# GarageRemote.net
KiCad netlist of a schematic drawn in EAGLE
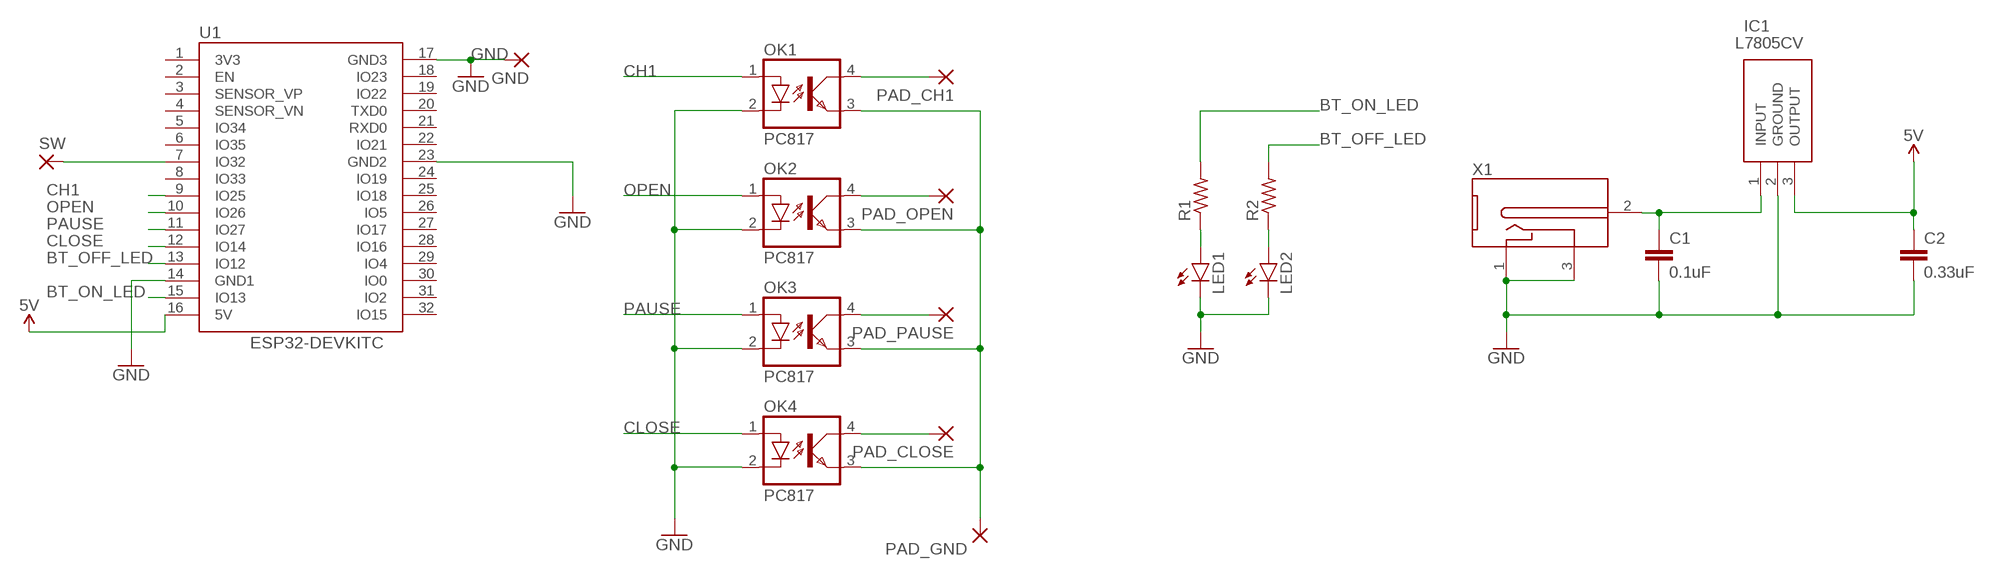
[diagram p0: schematic, sheet 1]

(export (version "E")
  (design (tool "Eeschema 10.0.6"))
  (components
    (comp (ref "C1")
      (value "0.1uF")
      (footprint "eagle-import:C2.5-2")
      (libsource (lib "eagle-import") (part "C2.5/2"))
    )
    (comp (ref "C2")
      (value "0.33uF")
      (footprint "eagle-import:C2.5-2")
      (libsource (lib "eagle-import") (part "C2.5/2"))
    )
    (comp (ref "GND")
      (value "2,54/1,0")
      (footprint "eagle-import:2,54_1,0")
      (libsource (lib "eagle-import") (part "2,54/1,0"))
    )
    (comp (ref "IC1")
      (value "L7805CV")
      (footprint "eagle-import:TO255P460X1020X2008-3P")
      (fields (field (name "MOUSER_PART_NUMBER") "511-L7805CV"))
      (libsource (lib "eagle-import") (part "L7805CV"))
    )
    (comp (ref "LED1")
      (value "LED5MM")
      (footprint "eagle-import:LED5MM")
      (libsource (lib "eagle-import") (part "LED5MM"))
    )
    (comp (ref "LED2")
      (value "LED5MM")
      (footprint "eagle-import:LED5MM")
      (libsource (lib "eagle-import") (part "LED5MM"))
    )
    (comp (ref "OK1")
      (value "PC817")
      (footprint "eagle-import:DIL04")
      (fields (field (name "MPN") "PC817X4J000F"))
      (libsource (lib "eagle-import") (part "PC817"))
    )
    (comp (ref "OK2")
      (value "PC817")
      (footprint "eagle-import:DIL04")
      (fields (field (name "MPN") "PC817X4J000F"))
      (libsource (lib "eagle-import") (part "PC817"))
    )
    (comp (ref "OK3")
      (value "PC817")
      (footprint "eagle-import:DIL04")
      (fields (field (name "MPN") "PC817X4J000F"))
      (libsource (lib "eagle-import") (part "PC817"))
    )
    (comp (ref "OK4")
      (value "PC817")
      (footprint "eagle-import:DIL04")
      (fields (field (name "MPN") "PC817X4J000F"))
      (libsource (lib "eagle-import") (part "PC817"))
    )
    (comp (ref "PAD_CH1")
      (value "2,54/1,0")
      (footprint "eagle-import:2,54_1,0")
      (libsource (lib "eagle-import") (part "2,54/1,0"))
    )
    (comp (ref "PAD_CLOSE")
      (value "2,54/1,0")
      (footprint "eagle-import:2,54_1,0")
      (libsource (lib "eagle-import") (part "2,54/1,0"))
    )
    (comp (ref "PAD_GND")
      (value "2,54/1,0")
      (footprint "eagle-import:2,54_1,0")
      (libsource (lib "eagle-import") (part "2,54/1,0"))
    )
    (comp (ref "PAD_OPEN")
      (value "2,54/1,0")
      (footprint "eagle-import:2,54_1,0")
      (libsource (lib "eagle-import") (part "2,54/1,0"))
    )
    (comp (ref "PAD_PAUSE")
      (value "2,54/1,0")
      (footprint "eagle-import:2,54_1,0")
      (libsource (lib "eagle-import") (part "2,54/1,0"))
    )
    (comp (ref "R1")
      (value "R-US_0204/5")
      (footprint "eagle-import:0204_5")
      (libsource (lib "eagle-import") (part "R-US_0204/5"))
    )
    (comp (ref "R2")
      (value "R-US_0204/5")
      (footprint "eagle-import:0204_5")
      (libsource (lib "eagle-import") (part "R-US_0204/5"))
    )
    (comp (ref "SW")
      (value "2,54/1,0")
      (footprint "eagle-import:2,54_1,0")
      (libsource (lib "eagle-import") (part "2,54/1,0"))
    )
    (comp (ref "U1")
      (value "ESP32-DEVKITC")
      (footprint "eagle-import:MODULE_ESP32-DEVKITC")
      (fields (field (name "MF") "Espressif Systems"))
      (libsource (lib "eagle-import") (part "ESP32-DEVKITC"))
    )
    (comp (ref "X1")
      (value "DC-2.1MM-5MM")
      (footprint "eagle-import:DC-21MM")
      (libsource (lib "eagle-import") (part "DC-5MM-2.1MM"))
    )
  )
  (nets
    (net (code "1") (name "/3V3") (class "Default")
      (node (ref "U1") (pin "1") (pinfunction "3V3_1") (pintype "power_in"))
    )
    (net (code "2") (name "/BT_OFF_LED") (class "Default")
      (node (ref "R2") (pin "2") (pinfunction "2_2") (pintype "passive"))
      (node (ref "U1") (pin "13") (pinfunction "IO12_13") (pintype "bidirectional"))
    )
    (net (code "3") (name "/BT_ON_LED") (class "Default")
      (node (ref "R1") (pin "2") (pinfunction "2_2") (pintype "passive"))
      (node (ref "U1") (pin "15") (pinfunction "IO13_15") (pintype "bidirectional"))
    )
    (net (code "4") (name "/CH1") (class "Default")
      (node (ref "OK1") (pin "1") (pinfunction "A_1") (pintype "passive"))
      (node (ref "U1") (pin "9") (pinfunction "IO25_9") (pintype "bidirectional"))
    )
    (net (code "5") (name "/CLOSE") (class "Default")
      (node (ref "OK4") (pin "1") (pinfunction "A_1") (pintype "passive"))
      (node (ref "U1") (pin "12") (pinfunction "IO14_12") (pintype "bidirectional"))
    )
    (net (code "6") (name "/OPEN") (class "Default")
      (node (ref "OK2") (pin "1") (pinfunction "A_1") (pintype "passive"))
      (node (ref "U1") (pin "10") (pinfunction "IO26_10") (pintype "bidirectional"))
    )
    (net (code "7") (name "/PAUSE") (class "Default")
      (node (ref "OK3") (pin "1") (pinfunction "A_1") (pintype "passive"))
      (node (ref "U1") (pin "11") (pinfunction "IO27_11") (pintype "bidirectional"))
    )
    (net (code "8") (name "5V") (class "Default")
      (node (ref "C2") (pin "1") (pinfunction "1_1") (pintype "passive"))
      (node (ref "IC1") (pin "3") (pinfunction "OUTPUT_3") (pintype "bidirectional"))
      (node (ref "U1") (pin "16") (pinfunction "5V_16") (pintype "bidirectional"))
    )
    (net (code "9") (name "GND") (class "Default")
      (node (ref "C1") (pin "2") (pinfunction "2_2") (pintype "passive"))
      (node (ref "C2") (pin "2") (pinfunction "2_2") (pintype "passive"))
      (node (ref "GND") (pin "1") (pinfunction "P_1") (pintype "passive"))
      (node (ref "IC1") (pin "2") (pinfunction "GROUND_2") (pintype "bidirectional"))
      (node (ref "LED1") (pin "K") (pinfunction "C_K") (pintype "passive"))
      (node (ref "LED2") (pin "K") (pinfunction "C_K") (pintype "passive"))
      (node (ref "OK1") (pin "2") (pinfunction "C_2") (pintype "passive"))
      (node (ref "OK2") (pin "2") (pinfunction "C_2") (pintype "passive"))
      (node (ref "OK3") (pin "2") (pinfunction "C_2") (pintype "passive"))
      (node (ref "OK4") (pin "2") (pinfunction "C_2") (pintype "passive"))
      (node (ref "U1") (pin "14") (pinfunction "GND1_14") (pintype "power_in"))
      (node (ref "U1") (pin "17") (pinfunction "GND3_17") (pintype "power_in"))
      (node (ref "U1") (pin "23") (pinfunction "GND2_23") (pintype "power_in"))
      (node (ref "X1") (pin "1") (pinfunction "1_1") (pintype "power_in"))
      (node (ref "X1") (pin "3") (pinfunction "2_3") (pintype "power_in"))
    )
    (net (code "10") (name "Net-(IC1-INPUT)") (class "Default")
      (node (ref "C1") (pin "1") (pinfunction "1_1") (pintype "passive"))
      (node (ref "IC1") (pin "1") (pinfunction "INPUT_1") (pintype "bidirectional"))
      (node (ref "X1") (pin "2") (pinfunction "3_2") (pintype "power_in"))
    )
    (net (code "11") (name "Net-(LED1-PadA)") (class "Default")
      (node (ref "LED1") (pin "A") (pinfunction "A_A") (pintype "passive"))
      (node (ref "R1") (pin "1") (pinfunction "1_1") (pintype "passive"))
    )
    (net (code "12") (name "Net-(LED2-PadA)") (class "Default")
      (node (ref "LED2") (pin "A") (pinfunction "A_A") (pintype "passive"))
      (node (ref "R2") (pin "1") (pinfunction "1_1") (pintype "passive"))
    )
    (net (code "13") (name "Net-(OK1-COL)") (class "Default")
      (node (ref "OK1") (pin "4") (pinfunction "COL_4") (pintype "passive"))
      (node (ref "PAD_CH1") (pin "1") (pinfunction "P_1") (pintype "passive"))
    )
    (net (code "14") (name "Net-(OK1-EMIT)") (class "Default")
      (node (ref "OK1") (pin "3") (pinfunction "EMIT_3") (pintype "passive"))
      (node (ref "OK2") (pin "3") (pinfunction "EMIT_3") (pintype "passive"))
      (node (ref "OK3") (pin "3") (pinfunction "EMIT_3") (pintype "passive"))
      (node (ref "OK4") (pin "3") (pinfunction "EMIT_3") (pintype "passive"))
      (node (ref "PAD_GND") (pin "1") (pinfunction "P_1") (pintype "passive"))
    )
    (net (code "15") (name "Net-(OK2-COL)") (class "Default")
      (node (ref "OK2") (pin "4") (pinfunction "COL_4") (pintype "passive"))
      (node (ref "PAD_OPEN") (pin "1") (pinfunction "P_1") (pintype "passive"))
    )
    (net (code "16") (name "Net-(OK3-COL)") (class "Default")
      (node (ref "OK3") (pin "4") (pinfunction "COL_4") (pintype "passive"))
      (node (ref "PAD_PAUSE") (pin "1") (pinfunction "P_1") (pintype "passive"))
    )
    (net (code "17") (name "Net-(OK4-COL)") (class "Default")
      (node (ref "OK4") (pin "4") (pinfunction "COL_4") (pintype "passive"))
      (node (ref "PAD_CLOSE") (pin "1") (pinfunction "P_1") (pintype "passive"))
    )
    (net (code "18") (name "Net-(SW-P)") (class "Default")
      (node (ref "SW") (pin "1") (pinfunction "P_1") (pintype "passive"))
      (node (ref "U1") (pin "7") (pinfunction "IO32_7") (pintype "bidirectional"))
    )
    (net (code "19") (name "unconnected-(U1-EN-Pad2)") (class "Default")
      (node (ref "U1") (pin "2") (pinfunction "EN_2") (pintype "input"))
    )
    (net (code "20") (name "unconnected-(U1-IO0-Pad30)") (class "Default")
      (node (ref "U1") (pin "30") (pinfunction "IO0_30") (pintype "bidirectional"))
    )
    (net (code "21") (name "unconnected-(U1-IO2-Pad31)") (class "Default")
      (node (ref "U1") (pin "31") (pinfunction "IO2_31") (pintype "bidirectional"))
    )
    (net (code "22") (name "unconnected-(U1-IO4-Pad29)") (class "Default")
      (node (ref "U1") (pin "29") (pinfunction "IO4_29") (pintype "bidirectional"))
    )
    (net (code "23") (name "unconnected-(U1-IO5-Pad26)") (class "Default")
      (node (ref "U1") (pin "26") (pinfunction "IO5_26") (pintype "bidirectional"))
    )
    (net (code "24") (name "unconnected-(U1-IO15-Pad32)") (class "Default")
      (node (ref "U1") (pin "32") (pinfunction "IO15_32") (pintype "bidirectional"))
    )
    (net (code "25") (name "unconnected-(U1-IO16-Pad28)") (class "Default")
      (node (ref "U1") (pin "28") (pinfunction "IO16_28") (pintype "bidirectional"))
    )
    (net (code "26") (name "unconnected-(U1-IO17-Pad27)") (class "Default")
      (node (ref "U1") (pin "27") (pinfunction "IO17_27") (pintype "bidirectional"))
    )
    (net (code "27") (name "unconnected-(U1-IO18-Pad25)") (class "Default")
      (node (ref "U1") (pin "25") (pinfunction "IO18_25") (pintype "bidirectional"))
    )
    (net (code "28") (name "unconnected-(U1-IO19-Pad24)") (class "Default")
      (node (ref "U1") (pin "24") (pinfunction "IO19_24") (pintype "bidirectional"))
    )
    (net (code "29") (name "unconnected-(U1-IO21-Pad22)") (class "Default")
      (node (ref "U1") (pin "22") (pinfunction "IO21_22") (pintype "bidirectional"))
    )
    (net (code "30") (name "unconnected-(U1-IO22-Pad19)") (class "Default")
      (node (ref "U1") (pin "19") (pinfunction "IO22_19") (pintype "bidirectional"))
    )
    (net (code "31") (name "unconnected-(U1-IO23-Pad18)") (class "Default")
      (node (ref "U1") (pin "18") (pinfunction "IO23_18") (pintype "bidirectional"))
    )
    (net (code "32") (name "unconnected-(U1-IO33-Pad8)") (class "Default")
      (node (ref "U1") (pin "8") (pinfunction "IO33_8") (pintype "bidirectional"))
    )
    (net (code "33") (name "unconnected-(U1-IO34-Pad5)") (class "Default")
      (node (ref "U1") (pin "5") (pinfunction "IO34_5") (pintype "bidirectional"))
    )
    (net (code "34") (name "unconnected-(U1-IO35-Pad6)") (class "Default")
      (node (ref "U1") (pin "6") (pinfunction "IO35_6") (pintype "bidirectional"))
    )
    (net (code "35") (name "unconnected-(U1-RXD0-Pad21)") (class "Default")
      (node (ref "U1") (pin "21") (pinfunction "RXD0_21") (pintype "input"))
    )
    (net (code "36") (name "unconnected-(U1-SENSOR_VN-Pad4)") (class "Default")
      (node (ref "U1") (pin "4") (pinfunction "SENSOR_VN_4") (pintype "input"))
    )
    (net (code "37") (name "unconnected-(U1-SENSOR_VP-Pad3)") (class "Default")
      (node (ref "U1") (pin "3") (pinfunction "SENSOR_VP_3") (pintype "input"))
    )
    (net (code "38") (name "unconnected-(U1-TXD0-Pad20)") (class "Default")
      (node (ref "U1") (pin "20") (pinfunction "TXD0_20") (pintype "output"))
    )
  )
)
